# pico.net
KiCad netlist of a schematic drawn in EAGLE
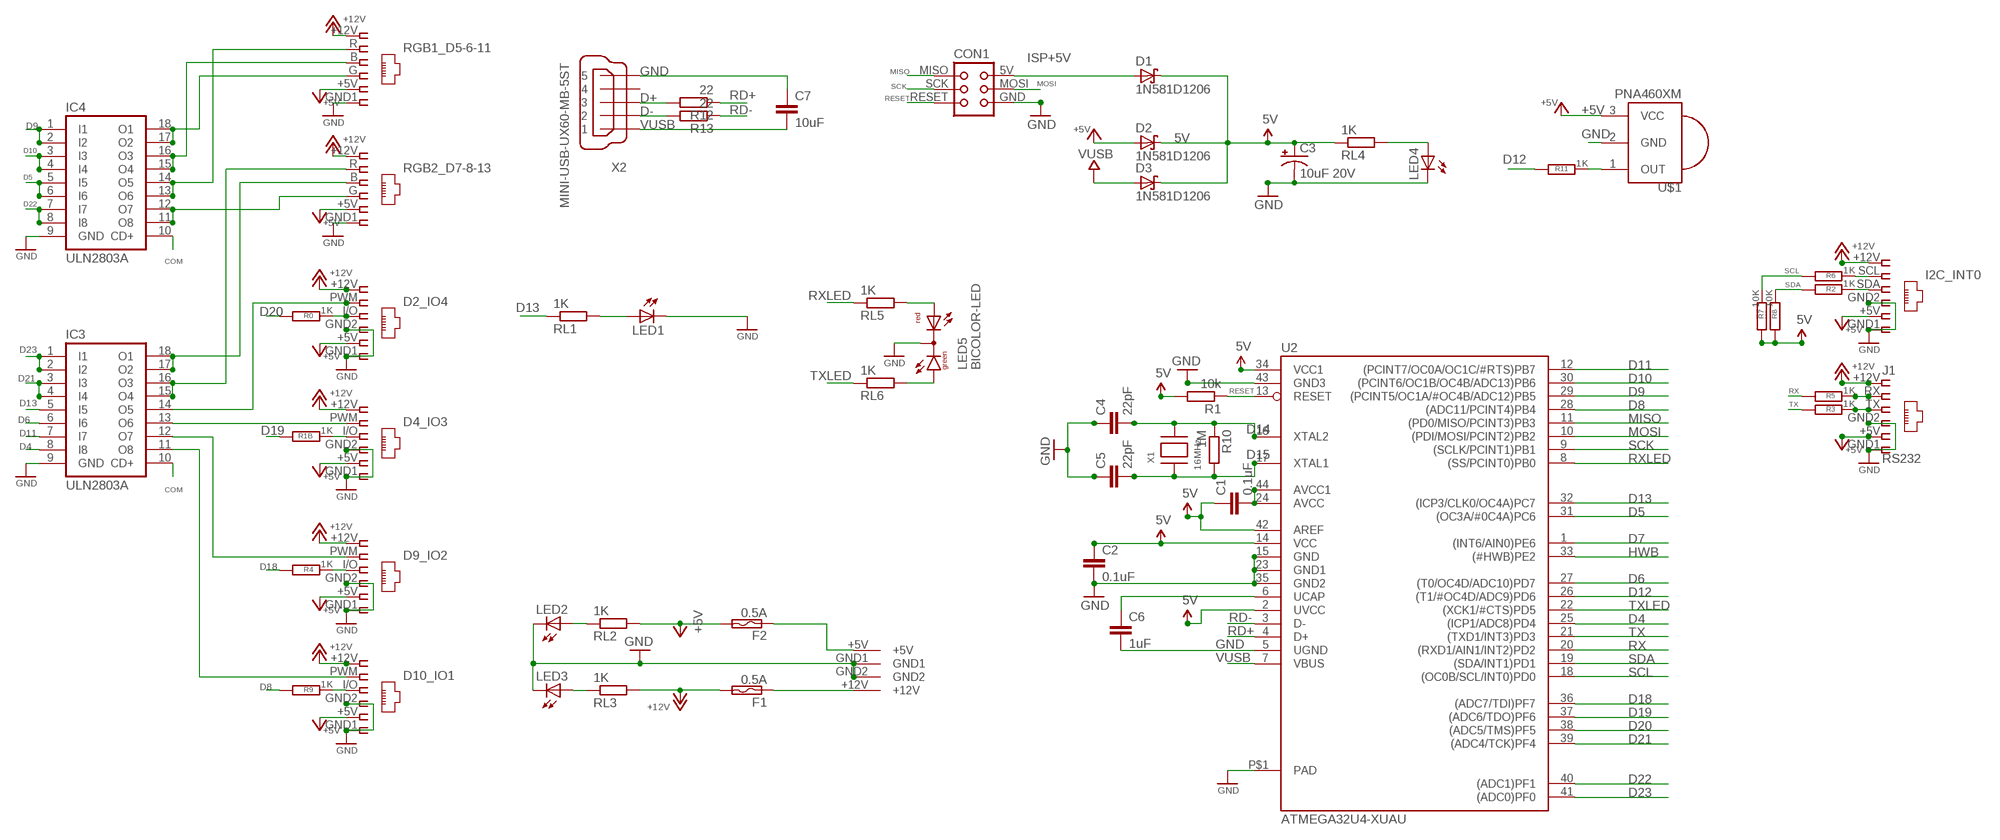
[diagram p0: schematic, sheet 1]

(export (version "E")
  (design (tool "Eeschema 10.0.6"))
  (components
    (comp (ref "C1")
      (value "0.1uF")
      (footprint "eagle-import:C1206")
      (libsource (lib "eagle-import") (part "C-EUC1206"))
    )
    (comp (ref "C2")
      (value "0.1uF")
      (footprint "eagle-import:C1206")
      (libsource (lib "eagle-import") (part "C-EUC1206"))
    )
    (comp (ref "C3")
      (value "10uF 20V")
      (footprint "eagle-import:EIA3216-KIT")
      (libsource (lib "eagle-import") (part "CAP_POL1206-KIT"))
    )
    (comp (ref "C4")
      (value "22pF")
      (footprint "eagle-import:C1206")
      (libsource (lib "eagle-import") (part "C-EUC1206"))
    )
    (comp (ref "C5")
      (value "22pF")
      (footprint "eagle-import:C1206")
      (libsource (lib "eagle-import") (part "C-EUC1206"))
    )
    (comp (ref "C6")
      (value "1uF")
      (footprint "eagle-import:C1206")
      (libsource (lib "eagle-import") (part "C-EUC1206"))
    )
    (comp (ref "C7")
      (value "10uF")
      (footprint "eagle-import:C1206")
      (libsource (lib "eagle-import") (part "C-EUC1206"))
    )
    (comp (ref "CON1")
      (value "TINYISPT")
      (footprint "eagle-import:TC2030-MCP-NL")
      (libsource (lib "eagle-import") (part "TINYISPT"))
    )
    (comp (ref "D1")
      (value "1N581D1206")
      (footprint "eagle-import:LED-1206")
      (libsource (lib "eagle-import") (part "1N581D1206"))
    )
    (comp (ref "D2")
      (value "1N581D1206")
      (footprint "eagle-import:LED-1206")
      (libsource (lib "eagle-import") (part "1N581D1206"))
    )
    (comp (ref "D2_IO4")
      (value "IO4")
      (footprint "eagle-import:RJ12-STRAIGHT")
      (libsource (lib "eagle-import") (part "RJ12STRAIGHT"))
    )
    (comp (ref "D3")
      (value "1N581D1206")
      (footprint "eagle-import:LED-1206")
      (libsource (lib "eagle-import") (part "1N581D1206"))
    )
    (comp (ref "D4_IO3")
      (value "IO3")
      (footprint "eagle-import:RJ12-STRAIGHT")
      (libsource (lib "eagle-import") (part "RJ12STRAIGHT"))
    )
    (comp (ref "D9_IO2")
      (value "IO2")
      (footprint "eagle-import:RJ12-STRAIGHT")
      (libsource (lib "eagle-import") (part "RJ12STRAIGHT"))
    )
    (comp (ref "D10_IO1")
      (value "IO1")
      (footprint "eagle-import:RJ12-STRAIGHT")
      (libsource (lib "eagle-import") (part "RJ12STRAIGHT"))
    )
    (comp (ref "F1")
      (value "0.5A")
      (footprint "eagle-import:C1812")
      (libsource (lib "eagle-import") (part "POLYSWITCHSMD1812"))
    )
    (comp (ref "F2")
      (value "0.5A")
      (footprint "eagle-import:C1812")
      (libsource (lib "eagle-import") (part "POLYSWITCHSMD1812"))
    )
    (comp (ref "I2C_INT0")
      (value "I2C")
      (footprint "eagle-import:RJ12-STRAIGHT-I2C")
      (libsource (lib "eagle-import") (part "RJ12STRAIGHT-I2C"))
    )
    (comp (ref "IC3")
      (value "ULN2803A")
      (footprint "eagle-import:SO18W")
      (libsource (lib "eagle-import") (part "ULN2803A"))
    )
    (comp (ref "IC4")
      (value "ULN2803A")
      (footprint "eagle-import:SO18W")
      (libsource (lib "eagle-import") (part "ULN2803A"))
    )
    (comp (ref "J1")
      (value "RS232")
      (footprint "eagle-import:RJ12-STRAIGHT-RS232")
      (libsource (lib "eagle-import") (part "RJ12STRAIGHT-RS232-SERVER"))
    )
    (comp (ref "LED1")
      (value "LED3MM")
      (footprint "eagle-import:LED3MM")
      (libsource (lib "eagle-import") (part "LED3MM"))
    )
    (comp (ref "LED2")
      (value "5V")
      (footprint "eagle-import:LED3MM")
      (libsource (lib "eagle-import") (part "LED3MM"))
    )
    (comp (ref "LED3")
      (value "12V")
      (footprint "eagle-import:LED3MM")
      (libsource (lib "eagle-import") (part "LED3MM"))
    )
    (comp (ref "LED4")
      (value "5V uC")
      (footprint "eagle-import:LED3MM")
      (libsource (lib "eagle-import") (part "LED3MM"))
    )
    (comp (ref "LED5")
      (value "BICOLOR-LED")
      (footprint "eagle-import:BICOLOR-3MM")
      (libsource (lib "eagle-import") (part "BICOLOR-LED"))
    )
    (comp (ref "R0")
      (value "1K")
      (footprint "eagle-import:M1206")
      (libsource (lib "eagle-import") (part "R-EU_M1206"))
    )
    (comp (ref "R1")
      (value "10k")
      (footprint "eagle-import:M1206")
      (libsource (lib "eagle-import") (part "R-EU_M1206"))
    )
    (comp (ref "R1B")
      (value "1K")
      (footprint "eagle-import:M1206")
      (libsource (lib "eagle-import") (part "R-EU_M1206"))
    )
    (comp (ref "R2")
      (value "1K")
      (footprint "eagle-import:M1206")
      (libsource (lib "eagle-import") (part "R-EU_M1206"))
    )
    (comp (ref "R3")
      (value "1K")
      (footprint "eagle-import:M1206")
      (libsource (lib "eagle-import") (part "R-EU_M1206"))
    )
    (comp (ref "R4")
      (value "1K")
      (footprint "eagle-import:M1206")
      (libsource (lib "eagle-import") (part "R-EU_M1206"))
    )
    (comp (ref "R5")
      (value "1K")
      (footprint "eagle-import:M1206")
      (libsource (lib "eagle-import") (part "R-EU_M1206"))
    )
    (comp (ref "R6")
      (value "1K")
      (footprint "eagle-import:M1206")
      (libsource (lib "eagle-import") (part "R-EU_M1206"))
    )
    (comp (ref "R7")
      (value "10K")
      (footprint "eagle-import:M1206")
      (libsource (lib "eagle-import") (part "R-EU_M1206"))
    )
    (comp (ref "R8")
      (value "10K")
      (footprint "eagle-import:M1206")
      (libsource (lib "eagle-import") (part "R-EU_M1206"))
    )
    (comp (ref "R9")
      (value "1K")
      (footprint "eagle-import:M1206")
      (libsource (lib "eagle-import") (part "R-EU_M1206"))
    )
    (comp (ref "R10")
      (value "1M")
      (footprint "eagle-import:M1206")
      (libsource (lib "eagle-import") (part "R-EU_M1206"))
    )
    (comp (ref "R11")
      (value "1K")
      (footprint "eagle-import:M1206")
      (libsource (lib "eagle-import") (part "R-EU_M1206"))
    )
    (comp (ref "R12")
      (value "22")
      (footprint "eagle-import:M1206")
      (libsource (lib "eagle-import") (part "R-EU_M1206"))
    )
    (comp (ref "R13")
      (value "22")
      (footprint "eagle-import:M1206")
      (libsource (lib "eagle-import") (part "R-EU_M1206"))
    )
    (comp (ref "RGB1_D5-6-11")
      (value "RGB1")
      (footprint "eagle-import:RJ12-STRAIGHT-RGB")
      (libsource (lib "eagle-import") (part "RJ12STRAIGHT-RGB"))
    )
    (comp (ref "RGB2_D7-8-13")
      (value "RGB2")
      (footprint "eagle-import:RJ12-STRAIGHT-RGB")
      (libsource (lib "eagle-import") (part "RJ12STRAIGHT-RGB"))
    )
    (comp (ref "RL1")
      (value "1K")
      (footprint "eagle-import:M1206")
      (libsource (lib "eagle-import") (part "R-EU_M1206"))
    )
    (comp (ref "RL2")
      (value "1K")
      (footprint "eagle-import:M1206")
      (libsource (lib "eagle-import") (part "R-EU_M1206"))
    )
    (comp (ref "RL3")
      (value "1K")
      (footprint "eagle-import:M1206")
      (libsource (lib "eagle-import") (part "R-EU_M1206"))
    )
    (comp (ref "RL4")
      (value "1K")
      (footprint "eagle-import:M1206")
      (libsource (lib "eagle-import") (part "R-EU_M1206"))
    )
    (comp (ref "RL5")
      (value "1K")
      (footprint "eagle-import:M1206")
      (libsource (lib "eagle-import") (part "R-EU_M1206"))
    )
    (comp (ref "RL6")
      (value "1K")
      (footprint "eagle-import:M1206")
      (libsource (lib "eagle-import") (part "R-EU_M1206"))
    )
    (comp (ref "U$1")
      (value "PNA460XM")
      (footprint "eagle-import:PNA460XM")
      (libsource (lib "eagle-import") (part "PNA460XM"))
    )
    (comp (ref "U$2")
      (value "KPJX-4S-S")
      (footprint "eagle-import:KPJX-4S-S")
      (libsource (lib "eagle-import") (part "KPJX-4S-S"))
    )
    (comp (ref "U2")
      (value "ATMEGA32U4-XUAU")
      (footprint "eagle-import:TQFP44-PAD")
      (libsource (lib "eagle-import") (part "ATMEGA32U4-XUAU"))
    )
    (comp (ref "X1")
      (value "16MHz")
      (footprint "eagle-import:NX6035")
      (libsource (lib "eagle-import") (part "XTALNX6035"))
    )
    (comp (ref "X2")
      (value "MINI-USB-UX60-MB-5ST")
      (footprint "eagle-import:UX60-MB-5ST")
      (libsource (lib "eagle-import") (part "MINI-USB-UX60-MB-5ST"))
    )
  )
  (nets
    (net (code "1") (name "+5V") (class "Default")
      (node (ref "D10_IO1") (pin "+5V") (pinfunction "5_+5V") (pintype "bidirectional"))
      (node (ref "D2") (pin "A") (pinfunction "A_A") (pintype "passive"))
      (node (ref "D2_IO4") (pin "+5V") (pinfunction "5_+5V") (pintype "bidirectional"))
      (node (ref "D4_IO3") (pin "+5V") (pinfunction "5_+5V") (pintype "bidirectional"))
      (node (ref "D9_IO2") (pin "+5V") (pinfunction "5_+5V") (pintype "bidirectional"))
      (node (ref "F2") (pin "2") (pinfunction "2_2") (pintype "passive"))
      (node (ref "I2C_INT0") (pin "+5V") (pinfunction "5_+5V") (pintype "bidirectional"))
      (node (ref "J1") (pin "+5V") (pinfunction "5_+5V") (pintype "bidirectional"))
      (node (ref "RGB1_D5-6-11") (pin "+5V") (pinfunction "5_+5V") (pintype "bidirectional"))
      (node (ref "RGB2_D7-8-13") (pin "+5V") (pinfunction "5_+5V") (pintype "bidirectional"))
      (node (ref "RL2") (pin "2") (pinfunction "2_2") (pintype "passive"))
      (node (ref "U$1") (pin "3") (pinfunction "VCC_3") (pintype "power_in"))
    )
    (net (code "2") (name "+12V") (class "Default")
      (node (ref "D10_IO1") (pin "+12V") (pinfunction "1_+12V") (pintype "bidirectional"))
      (node (ref "D2_IO4") (pin "+12V") (pinfunction "1_+12V") (pintype "bidirectional"))
      (node (ref "D4_IO3") (pin "+12V") (pinfunction "1_+12V") (pintype "bidirectional"))
      (node (ref "D9_IO2") (pin "+12V") (pinfunction "1_+12V") (pintype "bidirectional"))
      (node (ref "F1") (pin "2") (pinfunction "2_2") (pintype "passive"))
      (node (ref "I2C_INT0") (pin "+12V") (pinfunction "1_+12V") (pintype "bidirectional"))
      (node (ref "J1") (pin "+12V") (pinfunction "1_+12V") (pintype "bidirectional"))
      (node (ref "RGB1_D5-6-11") (pin "+12V") (pinfunction "1_+12V") (pintype "bidirectional"))
      (node (ref "RGB2_D7-8-13") (pin "+12V") (pinfunction "1_+12V") (pintype "bidirectional"))
      (node (ref "RL3") (pin "2") (pinfunction "2_2") (pintype "passive"))
    )
    (net (code "3") (name "/COM") (class "Default")
      (node (ref "IC3") (pin "10") (pinfunction "CD+_10") (pintype "passive"))
      (node (ref "IC4") (pin "10") (pinfunction "CD+_10") (pintype "passive"))
    )
    (net (code "4") (name "/D+") (class "Default")
      (node (ref "R12") (pin "2") (pinfunction "2_2") (pintype "passive"))
      (node (ref "X2") (pin "3") (pinfunction "3_3") (pintype "input"))
    )
    (net (code "5") (name "/D-") (class "Default")
      (node (ref "R13") (pin "2") (pinfunction "2_2") (pintype "passive"))
      (node (ref "X2") (pin "2") (pinfunction "2_2") (pintype "input"))
    )
    (net (code "6") (name "/D4") (class "Default")
      (node (ref "IC3") (pin "8") (pinfunction "I8_8") (pintype "input"))
      (node (ref "U2") (pin "25") (pinfunction "(ICP1/ADC8)PD4_25") (pintype "bidirectional"))
    )
    (net (code "7") (name "/D5") (class "Default")
      (node (ref "IC4") (pin "5") (pinfunction "I5_5") (pintype "input"))
      (node (ref "IC4") (pin "6") (pinfunction "I6_6") (pintype "input"))
      (node (ref "U2") (pin "31") (pinfunction "(OC3A/#0C4A)PC6_31") (pintype "bidirectional"))
    )
    (net (code "8") (name "/D6") (class "Default")
      (node (ref "IC3") (pin "6") (pinfunction "I6_6") (pintype "input"))
      (node (ref "U2") (pin "27") (pinfunction "(T0/OC4D/ADC10)PD7_27") (pintype "bidirectional"))
    )
    (net (code "9") (name "/D7") (class "Default")
      (node (ref "U2") (pin "1") (pinfunction "(INT6/AIN0)PE6_1") (pintype "bidirectional"))
    )
    (net (code "10") (name "/D8") (class "Default")
      (node (ref "R9") (pin "2") (pinfunction "2_2") (pintype "passive"))
      (node (ref "U2") (pin "28") (pinfunction "(ADC11/PCINT4)PB4_28") (pintype "bidirectional"))
    )
    (net (code "11") (name "/D9") (class "Default")
      (node (ref "IC4") (pin "1") (pinfunction "I1_1") (pintype "input"))
      (node (ref "IC4") (pin "2") (pinfunction "I2_2") (pintype "input"))
      (node (ref "U2") (pin "29") (pinfunction "(PCINT5/OC1A/#OC4B/ADC12)PB5_29") (pintype "bidirectional"))
    )
    (net (code "12") (name "/D10") (class "Default")
      (node (ref "IC4") (pin "3") (pinfunction "I3_3") (pintype "input"))
      (node (ref "IC4") (pin "4") (pinfunction "I4_4") (pintype "input"))
      (node (ref "U2") (pin "30") (pinfunction "(PCINT6/OC1B/OC4B/ADC13)PB6_30") (pintype "bidirectional"))
    )
    (net (code "13") (name "/D11") (class "Default")
      (node (ref "IC3") (pin "7") (pinfunction "I7_7") (pintype "input"))
      (node (ref "U2") (pin "12") (pinfunction "(PCINT7/OC0A/OC1C/#RTS)PB7_12") (pintype "bidirectional"))
    )
    (net (code "14") (name "/D12") (class "Default")
      (node (ref "R11") (pin "2") (pinfunction "2_2") (pintype "passive"))
      (node (ref "U2") (pin "26") (pinfunction "(T1/#OC4D/ADC9)PD6_26") (pintype "bidirectional"))
    )
    (net (code "15") (name "/D13") (class "Default")
      (node (ref "IC3") (pin "5") (pinfunction "I5_5") (pintype "input"))
      (node (ref "RL1") (pin "1") (pinfunction "1_1") (pintype "passive"))
      (node (ref "U2") (pin "32") (pinfunction "(ICP3/CLK0/OC4A)PC7_32") (pintype "bidirectional"))
    )
    (net (code "16") (name "/D14") (class "Default")
      (node (ref "C4") (pin "2") (pinfunction "2_2") (pintype "passive"))
      (node (ref "R10") (pin "1") (pinfunction "1_1") (pintype "passive"))
      (node (ref "U2") (pin "16") (pinfunction "XTAL2_16") (pintype "bidirectional"))
      (node (ref "X1") (pin "P$2") (pinfunction "P$2_P$2") (pintype "bidirectional"))
    )
    (net (code "17") (name "/D15") (class "Default")
      (node (ref "C5") (pin "2") (pinfunction "2_2") (pintype "passive"))
      (node (ref "R10") (pin "2") (pinfunction "2_2") (pintype "passive"))
      (node (ref "U2") (pin "17") (pinfunction "XTAL1_17") (pintype "bidirectional"))
      (node (ref "X1") (pin "P$1") (pinfunction "P$1_P$1") (pintype "bidirectional"))
    )
    (net (code "18") (name "/D18") (class "Default")
      (node (ref "R4") (pin "2") (pinfunction "2_2") (pintype "passive"))
      (node (ref "U2") (pin "36") (pinfunction "(ADC7/TDI)PF7_36") (pintype "bidirectional"))
    )
    (net (code "19") (name "/D19") (class "Default")
      (node (ref "R1B") (pin "2") (pinfunction "2_2") (pintype "passive"))
      (node (ref "U2") (pin "37") (pinfunction "(ADC6/TDO)PF6_37") (pintype "bidirectional"))
    )
    (net (code "20") (name "/D20") (class "Default")
      (node (ref "R0") (pin "2") (pinfunction "2_2") (pintype "passive"))
      (node (ref "U2") (pin "38") (pinfunction "(ADC5/TMS)PF5_38") (pintype "bidirectional"))
    )
    (net (code "21") (name "/D21") (class "Default")
      (node (ref "IC3") (pin "3") (pinfunction "I3_3") (pintype "input"))
      (node (ref "IC3") (pin "4") (pinfunction "I4_4") (pintype "input"))
      (node (ref "U2") (pin "39") (pinfunction "(ADC4/TCK)PF4_39") (pintype "bidirectional"))
    )
    (net (code "22") (name "/D22") (class "Default")
      (node (ref "IC4") (pin "7") (pinfunction "I7_7") (pintype "input"))
      (node (ref "IC4") (pin "8") (pinfunction "I8_8") (pintype "input"))
      (node (ref "U2") (pin "40") (pinfunction "(ADC1)PF1_40") (pintype "bidirectional"))
    )
    (net (code "23") (name "/D23") (class "Default")
      (node (ref "IC3") (pin "1") (pinfunction "I1_1") (pintype "input"))
      (node (ref "IC3") (pin "2") (pinfunction "I2_2") (pintype "input"))
      (node (ref "U2") (pin "41") (pinfunction "(ADC0)PF0_41") (pintype "bidirectional"))
    )
    (net (code "24") (name "/HWB") (class "Default")
      (node (ref "U2") (pin "33") (pinfunction "(#HWB)PE2_33") (pintype "bidirectional"))
    )
    (net (code "25") (name "/ISP+5V") (class "Default")
      (node (ref "CON1") (pin "5V") (pinfunction "VCC_5V") (pintype "passive"))
      (node (ref "D1") (pin "A") (pinfunction "A_A") (pintype "passive"))
    )
    (net (code "26") (name "/MISO") (class "Default")
      (node (ref "CON1") (pin "MISO") (pinfunction "MISO_MISO") (pintype "passive"))
      (node (ref "U2") (pin "11") (pinfunction "(PD0/MISO/PCINT3)PB3_11") (pintype "bidirectional"))
    )
    (net (code "27") (name "/MOSI") (class "Default")
      (node (ref "CON1") (pin "MOSI") (pinfunction "MOSI_MOSI") (pintype "passive"))
      (node (ref "U2") (pin "10") (pinfunction "(PDI/MOSI/PCINT2)PB2_10") (pintype "bidirectional"))
    )
    (net (code "28") (name "/RD+") (class "Default")
      (node (ref "R12") (pin "1") (pinfunction "1_1") (pintype "passive"))
      (node (ref "U2") (pin "4") (pinfunction "D+_4") (pintype "bidirectional"))
    )
    (net (code "29") (name "/RD-") (class "Default")
      (node (ref "R13") (pin "1") (pinfunction "1_1") (pintype "passive"))
      (node (ref "U2") (pin "3") (pinfunction "D-_3") (pintype "bidirectional"))
    )
    (net (code "30") (name "/RESET") (class "Default")
      (node (ref "CON1") (pin "RESET") (pinfunction "RESET_RESET") (pintype "passive"))
      (node (ref "R1") (pin "1") (pinfunction "1_1") (pintype "passive"))
      (node (ref "U2") (pin "13") (pinfunction "RESET_13") (pintype "input"))
    )
    (net (code "31") (name "/RX") (class "Default")
      (node (ref "R5") (pin "2") (pinfunction "2_2") (pintype "passive"))
      (node (ref "U2") (pin "20") (pinfunction "(RXD1/AIN1/INT2)PD2_20") (pintype "bidirectional"))
    )
    (net (code "32") (name "/RXLED") (class "Default")
      (node (ref "RL5") (pin "1") (pinfunction "1_1") (pintype "passive"))
      (node (ref "U2") (pin "8") (pinfunction "(SS/PCINT0)PB0_8") (pintype "bidirectional"))
    )
    (net (code "33") (name "/SCK") (class "Default")
      (node (ref "CON1") (pin "SCK") (pinfunction "SCK_SCK") (pintype "passive"))
      (node (ref "U2") (pin "9") (pinfunction "(SCLK/PCINT1)PB1_9") (pintype "bidirectional"))
    )
    (net (code "34") (name "/SCL") (class "Default")
      (node (ref "R6") (pin "2") (pinfunction "2_2") (pintype "passive"))
      (node (ref "R7") (pin "1") (pinfunction "1_1") (pintype "passive"))
      (node (ref "U2") (pin "18") (pinfunction "(OC0B/SCL/INT0)PD0_18") (pintype "bidirectional"))
    )
    (net (code "35") (name "/SDA") (class "Default")
      (node (ref "R2") (pin "2") (pinfunction "2_2") (pintype "passive"))
      (node (ref "R8") (pin "1") (pinfunction "1_1") (pintype "passive"))
      (node (ref "U2") (pin "19") (pinfunction "(SDA/INT1)PD1_19") (pintype "bidirectional"))
    )
    (net (code "36") (name "/TX") (class "Default")
      (node (ref "R3") (pin "2") (pinfunction "2_2") (pintype "passive"))
      (node (ref "U2") (pin "21") (pinfunction "(TXD1/INT3)PD3_21") (pintype "bidirectional"))
    )
    (net (code "37") (name "/TXLED") (class "Default")
      (node (ref "RL6") (pin "1") (pinfunction "1_1") (pintype "passive"))
      (node (ref "U2") (pin "22") (pinfunction "(XCK1/#CTS)PD5_22") (pintype "bidirectional"))
    )
    (net (code "38") (name "5V") (class "Default")
      (node (ref "C1") (pin "1") (pinfunction "1_1") (pintype "passive"))
      (node (ref "C2") (pin "1") (pinfunction "1_1") (pintype "passive"))
      (node (ref "C3") (pin "A") (pinfunction "+_A") (pintype "passive"))
      (node (ref "D1") (pin "C") (pinfunction "C_C") (pintype "passive"))
      (node (ref "D2") (pin "C") (pinfunction "C_C") (pintype "passive"))
      (node (ref "D3") (pin "C") (pinfunction "C_C") (pintype "passive"))
      (node (ref "R1") (pin "2") (pinfunction "2_2") (pintype "passive"))
      (node (ref "R7") (pin "2") (pinfunction "2_2") (pintype "passive"))
      (node (ref "R8") (pin "2") (pinfunction "2_2") (pintype "passive"))
      (node (ref "RL4") (pin "1") (pinfunction "1_1") (pintype "passive"))
      (node (ref "U2") (pin "14") (pinfunction "VCC_14") (pintype "power_in"))
      (node (ref "U2") (pin "2") (pinfunction "UVCC_2") (pintype "power_in"))
      (node (ref "U2") (pin "34") (pinfunction "VCC1_34") (pintype "power_in"))
      (node (ref "U2") (pin "42") (pinfunction "AREF_42") (pintype "power_in"))
    )
    (net (code "39") (name "GND") (class "Default")
      (node (ref "C2") (pin "2") (pinfunction "2_2") (pintype "passive"))
      (node (ref "C3") (pin "C") (pinfunction "-_C") (pintype "passive"))
      (node (ref "C4") (pin "1") (pinfunction "1_1") (pintype "passive"))
      (node (ref "C5") (pin "1") (pinfunction "1_1") (pintype "passive"))
      (node (ref "C6") (pin "2") (pinfunction "2_2") (pintype "passive"))
      (node (ref "C7") (pin "1") (pinfunction "1_1") (pintype "passive"))
      (node (ref "CON1") (pin "GND") (pinfunction "GND_GND") (pintype "passive"))
      (node (ref "D10_IO1") (pin "GND1") (pinfunction "6_GND1") (pintype "bidirectional"))
      (node (ref "D10_IO1") (pin "GND2") (pinfunction "4_GND2") (pintype "bidirectional"))
      (node (ref "D2_IO4") (pin "GND1") (pinfunction "6_GND1") (pintype "bidirectional"))
      (node (ref "D2_IO4") (pin "GND2") (pinfunction "4_GND2") (pintype "bidirectional"))
      (node (ref "D4_IO3") (pin "GND1") (pinfunction "6_GND1") (pintype "bidirectional"))
      (node (ref "D4_IO3") (pin "GND2") (pinfunction "4_GND2") (pintype "bidirectional"))
      (node (ref "D9_IO2") (pin "GND1") (pinfunction "6_GND1") (pintype "bidirectional"))
      (node (ref "D9_IO2") (pin "GND2") (pinfunction "4_GND2") (pintype "bidirectional"))
      (node (ref "I2C_INT0") (pin "GND1") (pinfunction "6_GND1") (pintype "bidirectional"))
      (node (ref "I2C_INT0") (pin "GND2") (pinfunction "4_GND2") (pintype "bidirectional"))
      (node (ref "IC3") (pin "9") (pinfunction "GND_9") (pintype "power_in"))
      (node (ref "IC4") (pin "9") (pinfunction "GND_9") (pintype "power_in"))
      (node (ref "J1") (pin "GND1") (pinfunction "6_GND1") (pintype "bidirectional"))
      (node (ref "J1") (pin "GND2") (pinfunction "4_GND2") (pintype "bidirectional"))
      (node (ref "LED1") (pin "K") (pinfunction "C_K") (pintype "passive"))
      (node (ref "LED2") (pin "K") (pinfunction "C_K") (pintype "passive"))
      (node (ref "LED3") (pin "K") (pinfunction "C_K") (pintype "passive"))
      (node (ref "LED4") (pin "K") (pinfunction "C_K") (pintype "passive"))
      (node (ref "LED5") (pin "2") (pinfunction "C_2") (pintype "passive"))
      (node (ref "RGB1_D5-6-11") (pin "GND1") (pinfunction "6_GND1") (pintype "bidirectional"))
      (node (ref "RGB2_D7-8-13") (pin "GND1") (pinfunction "6_GND1") (pintype "bidirectional"))
      (node (ref "U$1") (pin "2") (pinfunction "GND_2") (pintype "power_in"))
      (node (ref "U$2") (pin "GND1") (pinfunction "GND1_GND1") (pintype "input"))
      (node (ref "U$2") (pin "GND2") (pinfunction "GND2_GND2") (pintype "input"))
      (node (ref "U2") (pin "15") (pinfunction "GND_15") (pintype "power_in"))
      (node (ref "U2") (pin "23") (pinfunction "GND1_23") (pintype "power_in"))
      (node (ref "U2") (pin "35") (pinfunction "GND2_35") (pintype "power_in"))
      (node (ref "U2") (pin "43") (pinfunction "GND3_43") (pintype "power_in"))
      (node (ref "U2") (pin "5") (pinfunction "UGND_5") (pintype "power_in"))
      (node (ref "U2") (pin "P$1") (pinfunction "PAD_P$1") (pintype "power_in"))
      (node (ref "X2") (pin "5") (pinfunction "5_5") (pintype "input"))
    )
    (net (code "40") (name "Net-(D2_IO4-2)") (class "Default")
      (node (ref "D2_IO4") (pin "PWM") (pinfunction "2_PWM") (pintype "bidirectional"))
      (node (ref "IC3") (pin "14") (pinfunction "O5_14") (pintype "open_collector"))
    )
    (net (code "41") (name "Net-(D2_IO4-3)") (class "Default")
      (node (ref "D2_IO4") (pin "I/O") (pinfunction "3_I/O") (pintype "bidirectional"))
      (node (ref "R0") (pin "1") (pinfunction "1_1") (pintype "passive"))
    )
    (net (code "42") (name "Net-(D4_IO3-2)") (class "Default")
      (node (ref "D4_IO3") (pin "PWM") (pinfunction "2_PWM") (pintype "bidirectional"))
      (node (ref "IC3") (pin "13") (pinfunction "O6_13") (pintype "open_collector"))
    )
    (net (code "43") (name "Net-(D4_IO3-3)") (class "Default")
      (node (ref "D4_IO3") (pin "I/O") (pinfunction "3_I/O") (pintype "bidirectional"))
      (node (ref "R1B") (pin "1") (pinfunction "1_1") (pintype "passive"))
    )
    (net (code "44") (name "Net-(D9_IO2-2)") (class "Default")
      (node (ref "D9_IO2") (pin "PWM") (pinfunction "2_PWM") (pintype "bidirectional"))
      (node (ref "IC3") (pin "12") (pinfunction "O7_12") (pintype "open_collector"))
    )
    (net (code "45") (name "Net-(D9_IO2-3)") (class "Default")
      (node (ref "D9_IO2") (pin "I/O") (pinfunction "3_I/O") (pintype "bidirectional"))
      (node (ref "R4") (pin "1") (pinfunction "1_1") (pintype "passive"))
    )
    (net (code "46") (name "Net-(D10_IO1-2)") (class "Default")
      (node (ref "D10_IO1") (pin "PWM") (pinfunction "2_PWM") (pintype "bidirectional"))
      (node (ref "IC3") (pin "11") (pinfunction "O8_11") (pintype "open_collector"))
    )
    (net (code "47") (name "Net-(D10_IO1-3)") (class "Default")
      (node (ref "D10_IO1") (pin "I/O") (pinfunction "3_I/O") (pintype "bidirectional"))
      (node (ref "R9") (pin "1") (pinfunction "1_1") (pintype "passive"))
    )
    (net (code "48") (name "Net-(F1-Pad1)") (class "Default")
      (node (ref "F1") (pin "1") (pinfunction "1_1") (pintype "passive"))
      (node (ref "U$2") (pin "+12V") (pinfunction "+12V_+12V") (pintype "power_in"))
    )
    (net (code "49") (name "Net-(F2-Pad1)") (class "Default")
      (node (ref "F2") (pin "1") (pinfunction "1_1") (pintype "passive"))
      (node (ref "U$2") (pin "+5V") (pinfunction "+5V_+5V") (pintype "power_in"))
    )
    (net (code "50") (name "Net-(I2C_INT0-2)") (class "Default")
      (node (ref "I2C_INT0") (pin "SCL") (pinfunction "2_SCL") (pintype "bidirectional"))
      (node (ref "R6") (pin "1") (pinfunction "1_1") (pintype "passive"))
    )
    (net (code "51") (name "Net-(I2C_INT0-3)") (class "Default")
      (node (ref "I2C_INT0") (pin "SDA") (pinfunction "3_SDA") (pintype "bidirectional"))
      (node (ref "R2") (pin "1") (pinfunction "1_1") (pintype "passive"))
    )
    (net (code "52") (name "Net-(IC3-O1)") (class "Default")
      (node (ref "IC3") (pin "17") (pinfunction "O2_17") (pintype "open_collector"))
      (node (ref "IC3") (pin "18") (pinfunction "O1_18") (pintype "open_collector"))
      (node (ref "RGB2_D7-8-13") (pin "B") (pinfunction "3_B") (pintype "bidirectional"))
    )
    (net (code "53") (name "Net-(IC3-O3)") (class "Default")
      (node (ref "IC3") (pin "15") (pinfunction "O4_15") (pintype "open_collector"))
      (node (ref "IC3") (pin "16") (pinfunction "O3_16") (pintype "open_collector"))
      (node (ref "RGB2_D7-8-13") (pin "R") (pinfunction "2_R") (pintype "bidirectional"))
    )
    (net (code "54") (name "Net-(IC4-O1)") (class "Default")
      (node (ref "IC4") (pin "17") (pinfunction "O2_17") (pintype "open_collector"))
      (node (ref "IC4") (pin "18") (pinfunction "O1_18") (pintype "open_collector"))
      (node (ref "RGB1_D5-6-11") (pin "G") (pinfunction "4_G") (pintype "bidirectional"))
    )
    (net (code "55") (name "Net-(IC4-O3)") (class "Default")
      (node (ref "IC4") (pin "15") (pinfunction "O4_15") (pintype "open_collector"))
      (node (ref "IC4") (pin "16") (pinfunction "O3_16") (pintype "open_collector"))
      (node (ref "RGB1_D5-6-11") (pin "B") (pinfunction "3_B") (pintype "bidirectional"))
    )
    (net (code "56") (name "Net-(IC4-O5)") (class "Default")
      (node (ref "IC4") (pin "13") (pinfunction "O6_13") (pintype "open_collector"))
      (node (ref "IC4") (pin "14") (pinfunction "O5_14") (pintype "open_collector"))
      (node (ref "RGB1_D5-6-11") (pin "R") (pinfunction "2_R") (pintype "bidirectional"))
    )
    (net (code "57") (name "Net-(IC4-O7)") (class "Default")
      (node (ref "IC4") (pin "11") (pinfunction "O8_11") (pintype "open_collector"))
      (node (ref "IC4") (pin "12") (pinfunction "O7_12") (pintype "open_collector"))
      (node (ref "RGB2_D7-8-13") (pin "G") (pinfunction "4_G") (pintype "bidirectional"))
    )
    (net (code "58") (name "Net-(J1-2)") (class "Default")
      (node (ref "J1") (pin "RX") (pinfunction "2_RX") (pintype "bidirectional"))
      (node (ref "R5") (pin "1") (pinfunction "1_1") (pintype "passive"))
    )
    (net (code "59") (name "Net-(J1-3)") (class "Default")
      (node (ref "J1") (pin "TX") (pinfunction "3_TX") (pintype "bidirectional"))
      (node (ref "R3") (pin "1") (pinfunction "1_1") (pintype "passive"))
    )
    (net (code "60") (name "Net-(LED1-PadA)") (class "Default")
      (node (ref "LED1") (pin "A") (pinfunction "A_A") (pintype "passive"))
      (node (ref "RL1") (pin "2") (pinfunction "2_2") (pintype "passive"))
    )
    (net (code "61") (name "Net-(LED2-PadA)") (class "Default")
      (node (ref "LED2") (pin "A") (pinfunction "A_A") (pintype "passive"))
      (node (ref "RL2") (pin "1") (pinfunction "1_1") (pintype "passive"))
    )
    (net (code "62") (name "Net-(LED3-PadA)") (class "Default")
      (node (ref "LED3") (pin "A") (pinfunction "A_A") (pintype "passive"))
      (node (ref "RL3") (pin "1") (pinfunction "1_1") (pintype "passive"))
    )
    (net (code "63") (name "Net-(LED4-PadA)") (class "Default")
      (node (ref "LED4") (pin "A") (pinfunction "A_A") (pintype "passive"))
      (node (ref "RL4") (pin "2") (pinfunction "2_2") (pintype "passive"))
    )
    (net (code "64") (name "Net-(LED5-AG)") (class "Default")
      (node (ref "LED5") (pin "1") (pinfunction "AG_1") (pintype "passive"))
      (node (ref "RL6") (pin "2") (pinfunction "2_2") (pintype "passive"))
    )
    (net (code "65") (name "Net-(LED5-AR)") (class "Default")
      (node (ref "LED5") (pin "3") (pinfunction "AR_3") (pintype "passive"))
      (node (ref "RL5") (pin "2") (pinfunction "2_2") (pintype "passive"))
    )
    (net (code "66") (name "Net-(U$1-OUT)") (class "Default")
      (node (ref "R11") (pin "1") (pinfunction "1_1") (pintype "passive"))
      (node (ref "U$1") (pin "1") (pinfunction "OUT_1") (pintype "output"))
    )
    (net (code "67") (name "Net-(U2-AVCC)") (class "Default")
      (node (ref "C1") (pin "2") (pinfunction "2_2") (pintype "passive"))
      (node (ref "U2") (pin "24") (pinfunction "AVCC_24") (pintype "power_in"))
      (node (ref "U2") (pin "44") (pinfunction "AVCC1_44") (pintype "power_in"))
    )
    (net (code "68") (name "Net-(U2-UCAP)") (class "Default")
      (node (ref "C6") (pin "1") (pinfunction "1_1") (pintype "passive"))
      (node (ref "U2") (pin "6") (pinfunction "UCAP_6") (pintype "passive"))
    )
    (net (code "69") (name "VUSB") (class "Default")
      (node (ref "C7") (pin "2") (pinfunction "2_2") (pintype "passive"))
      (node (ref "D3") (pin "A") (pinfunction "A_A") (pintype "passive"))
      (node (ref "U2") (pin "7") (pinfunction "VBUS_7") (pintype "input"))
      (node (ref "X2") (pin "1") (pinfunction "1_1") (pintype "input"))
    )
    (net (code "70") (name "unconnected-(X2-Pad4)") (class "Default")
      (node (ref "X2") (pin "4") (pinfunction "4_4") (pintype "input"))
    )
  )
)
